# nodeLHC.net
KiCad netlist of a schematic drawn in EAGLE
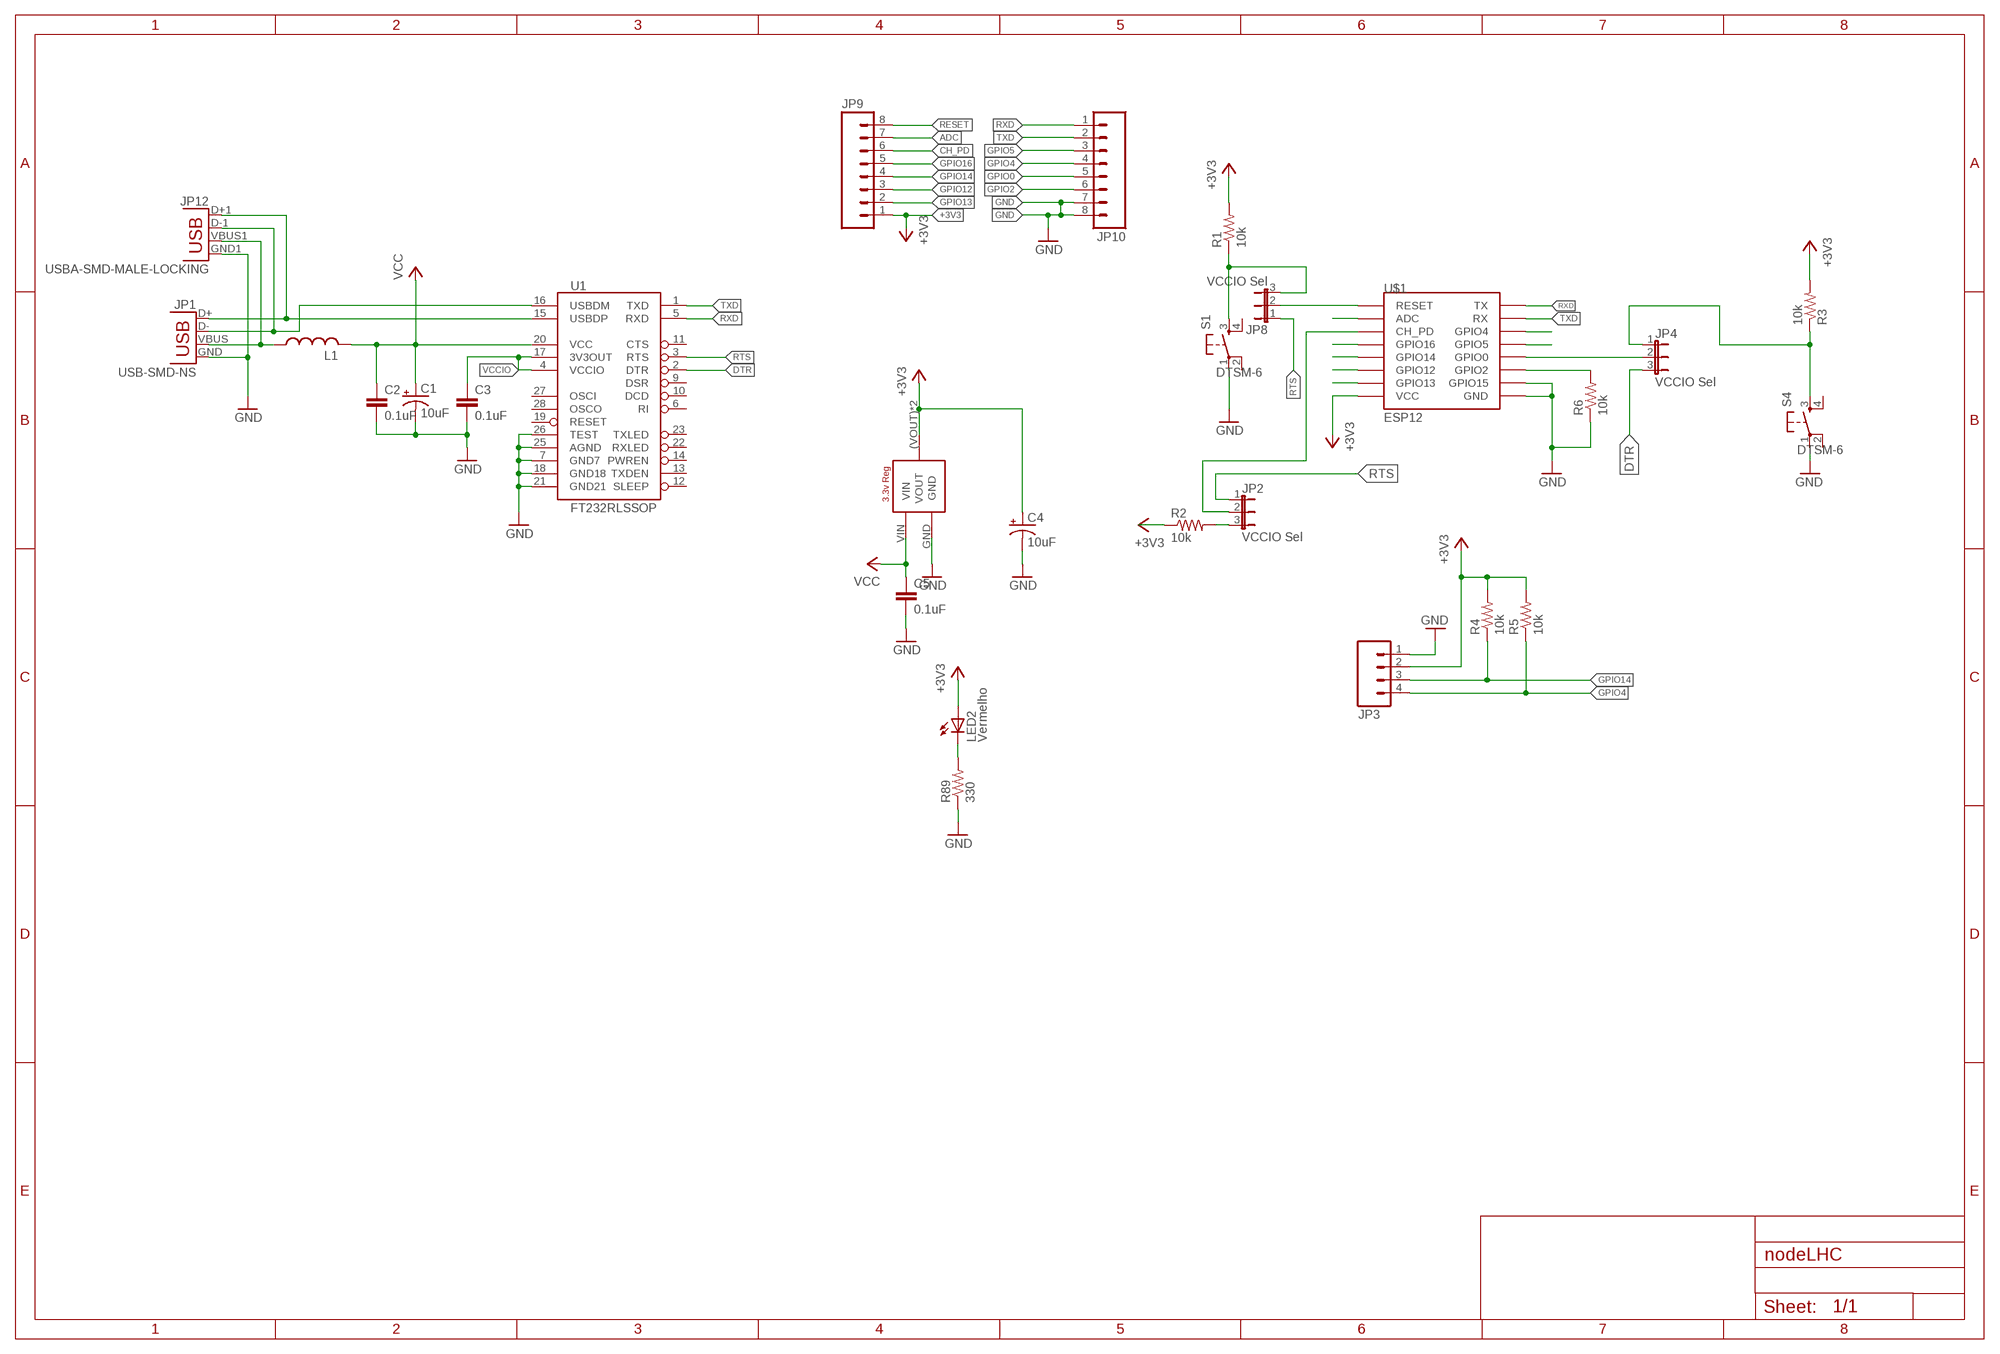
[diagram p0: schematic, sheet 1]

(export (version "E")
  (design (tool "Eeschema 10.0.6"))
  (components
    (comp (ref "C1")
      (value "10uF")
      (footprint "eagle-import:153CLV-0505")
      (libsource (lib "eagle-import") (part "CPOL-US153CLV-0505"))
    )
    (comp (ref "C2")
      (value "0.1uF")
      (footprint "eagle-import:C0603K")
      (libsource (lib "eagle-import") (part "C-EUC0603K"))
    )
    (comp (ref "C3")
      (value "0.1uF")
      (footprint "eagle-import:C0603K")
      (libsource (lib "eagle-import") (part "C-EUC0603K"))
    )
    (comp (ref "C4")
      (value "10uF")
      (footprint "eagle-import:153CLV-0505")
      (libsource (lib "eagle-import") (part "CPOL-US153CLV-0505"))
    )
    (comp (ref "C5")
      (value "0.1uF")
      (footprint "eagle-import:C0603K")
      (libsource (lib "eagle-import") (part "C-EUC0603K"))
    )
    (comp (ref "JP1")
      (value "USB-SMD-NS")
      (footprint "eagle-import:USB-MINIB-NOSTOP")
      (libsource (lib "eagle-import") (part "USB-SMD-NS"))
    )
    (comp (ref "JP2")
      (value "VCCIO Sel")
      (footprint "eagle-import:SJ_3")
      (libsource (lib "eagle-import") (part "JUMPER-3SMD"))
    )
    (comp (ref "JP3")
      (value "M04PTH")
      (footprint "eagle-import:1X04")
      (libsource (lib "eagle-import") (part "M04PTH"))
    )
    (comp (ref "JP4")
      (value "VCCIO Sel")
      (footprint "eagle-import:SJ_3")
      (libsource (lib "eagle-import") (part "JUMPER-3SMD"))
    )
    (comp (ref "JP8")
      (value "VCCIO Sel")
      (footprint "eagle-import:SJ_3")
      (libsource (lib "eagle-import") (part "JUMPER-3SMD"))
    )
    (comp (ref "JP9")
      (value "M08")
      (footprint "eagle-import:1X08_ROUND")
      (libsource (lib "eagle-import") (part "M08"))
    )
    (comp (ref "JP10")
      (value "M08")
      (footprint "eagle-import:1X08_ROUND")
      (libsource (lib "eagle-import") (part "M08"))
    )
    (comp (ref "JP12")
      (value "USBA-SMD-MALE-LOCKING")
      (footprint "eagle-import:USB-A-SMT-MALE-LOCKING")
      (libsource (lib "eagle-import") (part "USBA-SMD-MALE-LOCKING"))
    )
    (comp (ref "L1")
      (value "L-US")
      (footprint "eagle-import:C0603K")
      (libsource (lib "eagle-import") (part "L-US"))
    )
    (comp (ref "LED2")
      (value "Vermelho")
      (footprint "eagle-import:CHIP-LED0805")
      (libsource (lib "eagle-import") (part "LEDCHIP-LED0805"))
    )
    (comp (ref "R1")
      (value "10k")
      (footprint "eagle-import:R0603")
      (libsource (lib "eagle-import") (part "R-US_R0603"))
    )
    (comp (ref "R2")
      (value "10k")
      (footprint "eagle-import:R0603")
      (libsource (lib "eagle-import") (part "R-US_R0603"))
    )
    (comp (ref "R3")
      (value "10k")
      (footprint "eagle-import:R0603")
      (libsource (lib "eagle-import") (part "R-US_R0603"))
    )
    (comp (ref "R4")
      (value "10k")
      (footprint "eagle-import:R0603")
      (libsource (lib "eagle-import") (part "R-US_R0603"))
    )
    (comp (ref "R5")
      (value "10k")
      (footprint "eagle-import:R0603")
      (libsource (lib "eagle-import") (part "R-US_R0603"))
    )
    (comp (ref "R6")
      (value "10k")
      (footprint "eagle-import:R0603")
      (libsource (lib "eagle-import") (part "R-US_R0603"))
    )
    (comp (ref "R89")
      (value "330")
      (footprint "eagle-import:R0603")
      (libsource (lib "eagle-import") (part "R-US_R0603"))
    )
    (comp (ref "S1")
      (value "DTSM-6")
      (footprint "eagle-import:DTSM-6")
      (libsource (lib "eagle-import") (part "DTSM-6"))
    )
    (comp (ref "S4")
      (value "DTSM-6")
      (footprint "eagle-import:DTSM-6")
      (libsource (lib "eagle-import") (part "DTSM-6"))
    )
    (comp (ref "U$1")
      (value "ESP12")
      (footprint "eagle-import:ESP12")
      (libsource (lib "eagle-import") (part "ESP12"))
    )
    (comp (ref "U$2")
      (value "LD1117")
      (footprint "eagle-import:LD1117SOT-223")
      (libsource (lib "eagle-import") (part "LD1117"))
    )
    (comp (ref "U1")
      (value "FT232RLSSOP")
      (footprint "eagle-import:SSOP28DB")
      (libsource (lib "eagle-import") (part "FT232RLSSOP"))
    )
  )
  (nets
    (net (code "1") (name "+3V3") (class "Default")
      (node (ref "C4") (pin "+") (pinfunction "+_+") (pintype "passive"))
      (node (ref "JP3") (pin "2") (pinfunction "2_2") (pintype "passive"))
      (node (ref "JP9") (pin "1") (pinfunction "1_1") (pintype "passive"))
      (node (ref "LED2") (pin "A") (pinfunction "A_A") (pintype "passive"))
      (node (ref "R1") (pin "2") (pinfunction "2_2") (pintype "passive"))
      (node (ref "R2") (pin "1") (pinfunction "1_1") (pintype "passive"))
      (node (ref "R3") (pin "2") (pinfunction "2_2") (pintype "passive"))
      (node (ref "R4") (pin "2") (pinfunction "2_2") (pintype "passive"))
      (node (ref "R5") (pin "2") (pinfunction "2_2") (pintype "passive"))
      (node (ref "U$1") (pin "VCC") (pinfunction "VCC_VCC") (pintype "bidirectional"))
      (node (ref "U$2") (pin "(VOUT)") (pinfunction "VOUT_(VOUT)") (pintype "bidirectional"))
      (node (ref "U$2") (pin "VOUT") (pinfunction "VOUT_VOUT") (pintype "bidirectional"))
    )
    (net (code "2") (name "ADC") (class "Default")
      (node (ref "JP9") (pin "7") (pinfunction "7_7") (pintype "passive"))
      (node (ref "U$1") (pin "ADC") (pinfunction "ADC_ADC") (pintype "bidirectional"))
    )
    (net (code "3") (name "CH_PD") (class "Default")
      (node (ref "JP2") (pin "2") (pinfunction "2_2") (pintype "passive"))
      (node (ref "JP9") (pin "6") (pinfunction "6_6") (pintype "passive"))
      (node (ref "U$1") (pin "CH_PD") (pinfunction "CH_PD_CH_PD") (pintype "bidirectional"))
    )
    (net (code "4") (name "DTR") (class "Default")
      (node (ref "JP4") (pin "3") (pinfunction "3_3") (pintype "passive"))
      (node (ref "U1") (pin "2") (pinfunction "DTR_2") (pintype "output"))
    )
    (net (code "5") (name "GND") (class "Default")
      (node (ref "C1") (pin "-") (pinfunction "-_-") (pintype "passive"))
      (node (ref "C2") (pin "2") (pinfunction "2_2") (pintype "passive"))
      (node (ref "C3") (pin "2") (pinfunction "2_2") (pintype "passive"))
      (node (ref "C4") (pin "-") (pinfunction "-_-") (pintype "passive"))
      (node (ref "C5") (pin "2") (pinfunction "2_2") (pintype "passive"))
      (node (ref "JP1") (pin "GND") (pinfunction "GND_GND") (pintype "bidirectional"))
      (node (ref "JP10") (pin "7") (pinfunction "7_7") (pintype "passive"))
      (node (ref "JP10") (pin "8") (pinfunction "8_8") (pintype "passive"))
      (node (ref "JP12") (pin "GND1") (pinfunction "GND_GND1") (pintype "bidirectional"))
      (node (ref "JP3") (pin "1") (pinfunction "1_1") (pintype "passive"))
      (node (ref "R6") (pin "1") (pinfunction "1_1") (pintype "passive"))
      (node (ref "R89") (pin "1") (pinfunction "1_1") (pintype "passive"))
      (node (ref "S1") (pin "1") (pinfunction "1_1") (pintype "passive"))
      (node (ref "S4") (pin "1") (pinfunction "1_1") (pintype "passive"))
      (node (ref "U$1") (pin "GND") (pinfunction "GND_GND") (pintype "bidirectional"))
      (node (ref "U$1") (pin "GPIO15") (pinfunction "GPIO15_GPIO15") (pintype "bidirectional"))
      (node (ref "U$2") (pin "GND") (pinfunction "GND_GND") (pintype "bidirectional"))
      (node (ref "U1") (pin "18") (pinfunction "GND18_18") (pintype "power_in"))
      (node (ref "U1") (pin "21") (pinfunction "GND21_21") (pintype "power_in"))
      (node (ref "U1") (pin "25") (pinfunction "AGND_25") (pintype "power_in"))
      (node (ref "U1") (pin "26") (pinfunction "TEST_26") (pintype "input"))
      (node (ref "U1") (pin "7") (pinfunction "GND7_7") (pintype "power_in"))
    )
    (net (code "6") (name "GPIO0") (class "Default")
      (node (ref "JP10") (pin "5") (pinfunction "5_5") (pintype "passive"))
      (node (ref "JP4") (pin "2") (pinfunction "2_2") (pintype "passive"))
      (node (ref "U$1") (pin "GPIO0") (pinfunction "GPIO0_GPIO0") (pintype "bidirectional"))
    )
    (net (code "7") (name "GPIO2") (class "Default")
      (node (ref "JP10") (pin "6") (pinfunction "6_6") (pintype "passive"))
      (node (ref "R6") (pin "2") (pinfunction "2_2") (pintype "passive"))
      (node (ref "U$1") (pin "GPIO2") (pinfunction "GPIO2_GPIO2") (pintype "bidirectional"))
    )
    (net (code "8") (name "GPIO4") (class "Default")
      (node (ref "JP10") (pin "4") (pinfunction "4_4") (pintype "passive"))
      (node (ref "JP3") (pin "4") (pinfunction "4_4") (pintype "passive"))
      (node (ref "R5") (pin "1") (pinfunction "1_1") (pintype "passive"))
      (node (ref "U$1") (pin "GPIO5") (pinfunction "GPIO5_GPIO5") (pintype "bidirectional"))
    )
    (net (code "9") (name "GPIO5") (class "Default")
      (node (ref "JP10") (pin "3") (pinfunction "3_3") (pintype "passive"))
      (node (ref "U$1") (pin "GPIO4") (pinfunction "GPIO4_GPIO4") (pintype "bidirectional"))
    )
    (net (code "10") (name "GPIO12") (class "Default")
      (node (ref "JP9") (pin "3") (pinfunction "3_3") (pintype "passive"))
      (node (ref "U$1") (pin "GPIO12") (pinfunction "GPIO12_GPIO12") (pintype "bidirectional"))
    )
    (net (code "11") (name "GPIO13") (class "Default")
      (node (ref "JP9") (pin "2") (pinfunction "2_2") (pintype "passive"))
      (node (ref "U$1") (pin "GPIO13") (pinfunction "GPIO13_GPIO13") (pintype "bidirectional"))
    )
    (net (code "12") (name "GPIO14") (class "Default")
      (node (ref "JP3") (pin "3") (pinfunction "3_3") (pintype "passive"))
      (node (ref "JP9") (pin "4") (pinfunction "4_4") (pintype "passive"))
      (node (ref "R4") (pin "1") (pinfunction "1_1") (pintype "passive"))
      (node (ref "U$1") (pin "GPIO14") (pinfunction "GPIO14_GPIO14") (pintype "bidirectional"))
    )
    (net (code "13") (name "GPIO16") (class "Default")
      (node (ref "JP9") (pin "5") (pinfunction "5_5") (pintype "passive"))
      (node (ref "U$1") (pin "GPIO16") (pinfunction "GPIO16_GPIO16") (pintype "bidirectional"))
    )
    (net (code "14") (name "Net-(JP2-Pad3)") (class "Default")
      (node (ref "JP2") (pin "3") (pinfunction "3_3") (pintype "passive"))
      (node (ref "R2") (pin "2") (pinfunction "2_2") (pintype "passive"))
    )
    (net (code "15") (name "Net-(JP4-Pad1)") (class "Default")
      (node (ref "JP4") (pin "1") (pinfunction "1_1") (pintype "passive"))
      (node (ref "R3") (pin "1") (pinfunction "1_1") (pintype "passive"))
      (node (ref "S4") (pin "3") (pinfunction "3_3") (pintype "passive"))
    )
    (net (code "16") (name "Net-(JP8-Pad3)") (class "Default")
      (node (ref "JP8") (pin "3") (pinfunction "3_3") (pintype "passive"))
      (node (ref "R1") (pin "1") (pinfunction "1_1") (pintype "passive"))
      (node (ref "S1") (pin "3") (pinfunction "3_3") (pintype "passive"))
    )
    (net (code "17") (name "Net-(JP12-D+)") (class "Default")
      (node (ref "JP1") (pin "D+") (pinfunction "D+_D+") (pintype "bidirectional"))
      (node (ref "JP12") (pin "D+1") (pinfunction "D+_D+1") (pintype "bidirectional"))
      (node (ref "U1") (pin "15") (pinfunction "USBDP_15") (pintype "bidirectional"))
    )
    (net (code "18") (name "Net-(JP12-D-)") (class "Default")
      (node (ref "JP1") (pin "D-") (pinfunction "D-_D-") (pintype "bidirectional"))
      (node (ref "JP12") (pin "D-1") (pinfunction "D-_D-1") (pintype "bidirectional"))
      (node (ref "U1") (pin "16") (pinfunction "USBDM_16") (pintype "bidirectional"))
    )
    (net (code "19") (name "Net-(JP12-VBUS)") (class "Default")
      (node (ref "JP1") (pin "VBUS") (pinfunction "VBUS_VBUS") (pintype "bidirectional"))
      (node (ref "JP12") (pin "VBUS1") (pinfunction "VBUS_VBUS1") (pintype "bidirectional"))
      (node (ref "L1") (pin "1") (pinfunction "1_1") (pintype "passive"))
    )
    (net (code "20") (name "Net-(LED2-PadC)") (class "Default")
      (node (ref "LED2") (pin "C") (pinfunction "C_C") (pintype "passive"))
      (node (ref "R89") (pin "2") (pinfunction "2_2") (pintype "passive"))
    )
    (net (code "21") (name "RESET") (class "Default")
      (node (ref "JP8") (pin "2") (pinfunction "2_2") (pintype "passive"))
      (node (ref "JP9") (pin "8") (pinfunction "8_8") (pintype "passive"))
      (node (ref "U$1") (pin "RESET") (pinfunction "RESET_RESET") (pintype "bidirectional"))
    )
    (net (code "22") (name "RTS") (class "Default")
      (node (ref "JP2") (pin "1") (pinfunction "1_1") (pintype "passive"))
      (node (ref "JP8") (pin "1") (pinfunction "1_1") (pintype "passive"))
      (node (ref "U1") (pin "3") (pinfunction "RTS_3") (pintype "output"))
    )
    (net (code "23") (name "RXD") (class "Default")
      (node (ref "JP10") (pin "1") (pinfunction "1_1") (pintype "passive"))
      (node (ref "U$1") (pin "TX") (pinfunction "TX_TX") (pintype "bidirectional"))
      (node (ref "U1") (pin "5") (pinfunction "RXD_5") (pintype "input"))
    )
    (net (code "24") (name "TXD") (class "Default")
      (node (ref "JP10") (pin "2") (pinfunction "2_2") (pintype "passive"))
      (node (ref "U$1") (pin "RX") (pinfunction "RX_RX") (pintype "bidirectional"))
      (node (ref "U1") (pin "1") (pinfunction "TXD_1") (pintype "output"))
    )
    (net (code "25") (name "VCC") (class "Default")
      (node (ref "C1") (pin "+") (pinfunction "+_+") (pintype "passive"))
      (node (ref "C2") (pin "1") (pinfunction "1_1") (pintype "passive"))
      (node (ref "C5") (pin "1") (pinfunction "1_1") (pintype "passive"))
      (node (ref "L1") (pin "2") (pinfunction "2_2") (pintype "passive"))
      (node (ref "U$2") (pin "VIN") (pinfunction "VIN_VIN") (pintype "bidirectional"))
      (node (ref "U1") (pin "20") (pinfunction "VCC_20") (pintype "power_in"))
    )
    (net (code "26") (name "VCCIO") (class "Default")
      (node (ref "C3") (pin "1") (pinfunction "1_1") (pintype "passive"))
      (node (ref "U1") (pin "17") (pinfunction "3V3OUT_17") (pintype "output"))
      (node (ref "U1") (pin "4") (pinfunction "VCCIO_4") (pintype "power_in"))
    )
    (net (code "27") (name "unconnected-(S1-Pad2)") (class "Default")
      (node (ref "S1") (pin "2") (pinfunction "2_2") (pintype "passive"))
    )
    (net (code "28") (name "unconnected-(S1-Pad4)") (class "Default")
      (node (ref "S1") (pin "4") (pinfunction "4_4") (pintype "passive"))
    )
    (net (code "29") (name "unconnected-(S4-Pad2)") (class "Default")
      (node (ref "S4") (pin "2") (pinfunction "2_2") (pintype "passive"))
    )
    (net (code "30") (name "unconnected-(S4-Pad4)") (class "Default")
      (node (ref "S4") (pin "4") (pinfunction "4_4") (pintype "passive"))
    )
    (net (code "31") (name "unconnected-(U1-CTS-Pad11)") (class "Default")
      (node (ref "U1") (pin "11") (pinfunction "CTS_11") (pintype "input"))
    )
    (net (code "32") (name "unconnected-(U1-DCD-Pad10)") (class "Default")
      (node (ref "U1") (pin "10") (pinfunction "DCD_10") (pintype "input"))
    )
    (net (code "33") (name "unconnected-(U1-DSR-Pad9)") (class "Default")
      (node (ref "U1") (pin "9") (pinfunction "DSR_9") (pintype "input"))
    )
    (net (code "34") (name "unconnected-(U1-OSCI-Pad27)") (class "Default")
      (node (ref "U1") (pin "27") (pinfunction "OSCI_27") (pintype "input"))
    )
    (net (code "35") (name "unconnected-(U1-OSCO-Pad28)") (class "Default")
      (node (ref "U1") (pin "28") (pinfunction "OSCO_28") (pintype "output"))
    )
    (net (code "36") (name "unconnected-(U1-PWREN-Pad14)") (class "Default")
      (node (ref "U1") (pin "14") (pinfunction "PWREN_14") (pintype "input"))
    )
    (net (code "37") (name "unconnected-(U1-RESET-Pad19)") (class "Default")
      (node (ref "U1") (pin "19") (pinfunction "RESET_19") (pintype "input"))
    )
    (net (code "38") (name "unconnected-(U1-RI-Pad6)") (class "Default")
      (node (ref "U1") (pin "6") (pinfunction "RI_6") (pintype "input"))
    )
    (net (code "39") (name "unconnected-(U1-RXLED-Pad22)") (class "Default")
      (node (ref "U1") (pin "22") (pinfunction "RXLED_22") (pintype "input"))
    )
    (net (code "40") (name "unconnected-(U1-SLEEP-Pad12)") (class "Default")
      (node (ref "U1") (pin "12") (pinfunction "SLEEP_12") (pintype "input"))
    )
    (net (code "41") (name "unconnected-(U1-TXDEN-Pad13)") (class "Default")
      (node (ref "U1") (pin "13") (pinfunction "TXDEN_13") (pintype "input"))
    )
    (net (code "42") (name "unconnected-(U1-TXLED-Pad23)") (class "Default")
      (node (ref "U1") (pin "23") (pinfunction "TXLED_23") (pintype "input"))
    )
  )
)
